# usbctest.net
KiCad netlist of a schematic drawn in EAGLE
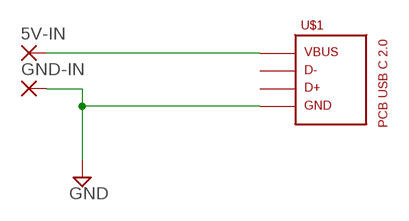
[diagram p0: schematic, sheet 1]

(export (version "E")
  (design (tool "Eeschema 10.0.6"))
  (components
    (comp (ref "5V-IN")
      (value "2,54/0,9")
      (footprint "eagle-import:2,54_0,9")
      (libsource (lib "eagle-import") (part "2,54/0,9"))
    )
    (comp (ref "GND-IN")
      (value "2,54/0,9")
      (footprint "eagle-import:2,54_0,9")
      (libsource (lib "eagle-import") (part "2,54/0,9"))
    )
    (comp (ref "U$1")
      (value "PCB_USB_C_2.0W_2")
      (footprint "eagle-import:USB_TYPE_C_W_2.0_2")
      (libsource (lib "eagle-import") (part "PCB_USB_C_2.0W_2"))
    )
  )
  (nets
    (net (code "1") (name "GND") (class "Default")
      (node (ref "GND-IN") (pin "1") (pinfunction "P_1") (pintype "passive"))
      (node (ref "U$1") (pin "GND") (pinfunction "GND_GND") (pintype "bidirectional"))
    )
    (net (code "2") (name "Net-(5V-IN-P)") (class "Default")
      (node (ref "5V-IN") (pin "1") (pinfunction "P_1") (pintype "passive"))
      (node (ref "U$1") (pin "VBUS") (pinfunction "VBUS_VBUS") (pintype "bidirectional"))
    )
    (net (code "3") (name "unconnected-(U$1-PadD+)") (class "Default")
      (node (ref "U$1") (pin "D+") (pinfunction "D+_D+") (pintype "bidirectional"))
    )
    (net (code "4") (name "unconnected-(U$1-PadD-)") (class "Default")
      (node (ref "U$1") (pin "D-") (pinfunction "D-_D-") (pintype "bidirectional"))
    )
  )
)
